# ESP32_2_0_2024-08-18.net
KiCad netlist of a schematic drawn in EasyEDA Pro
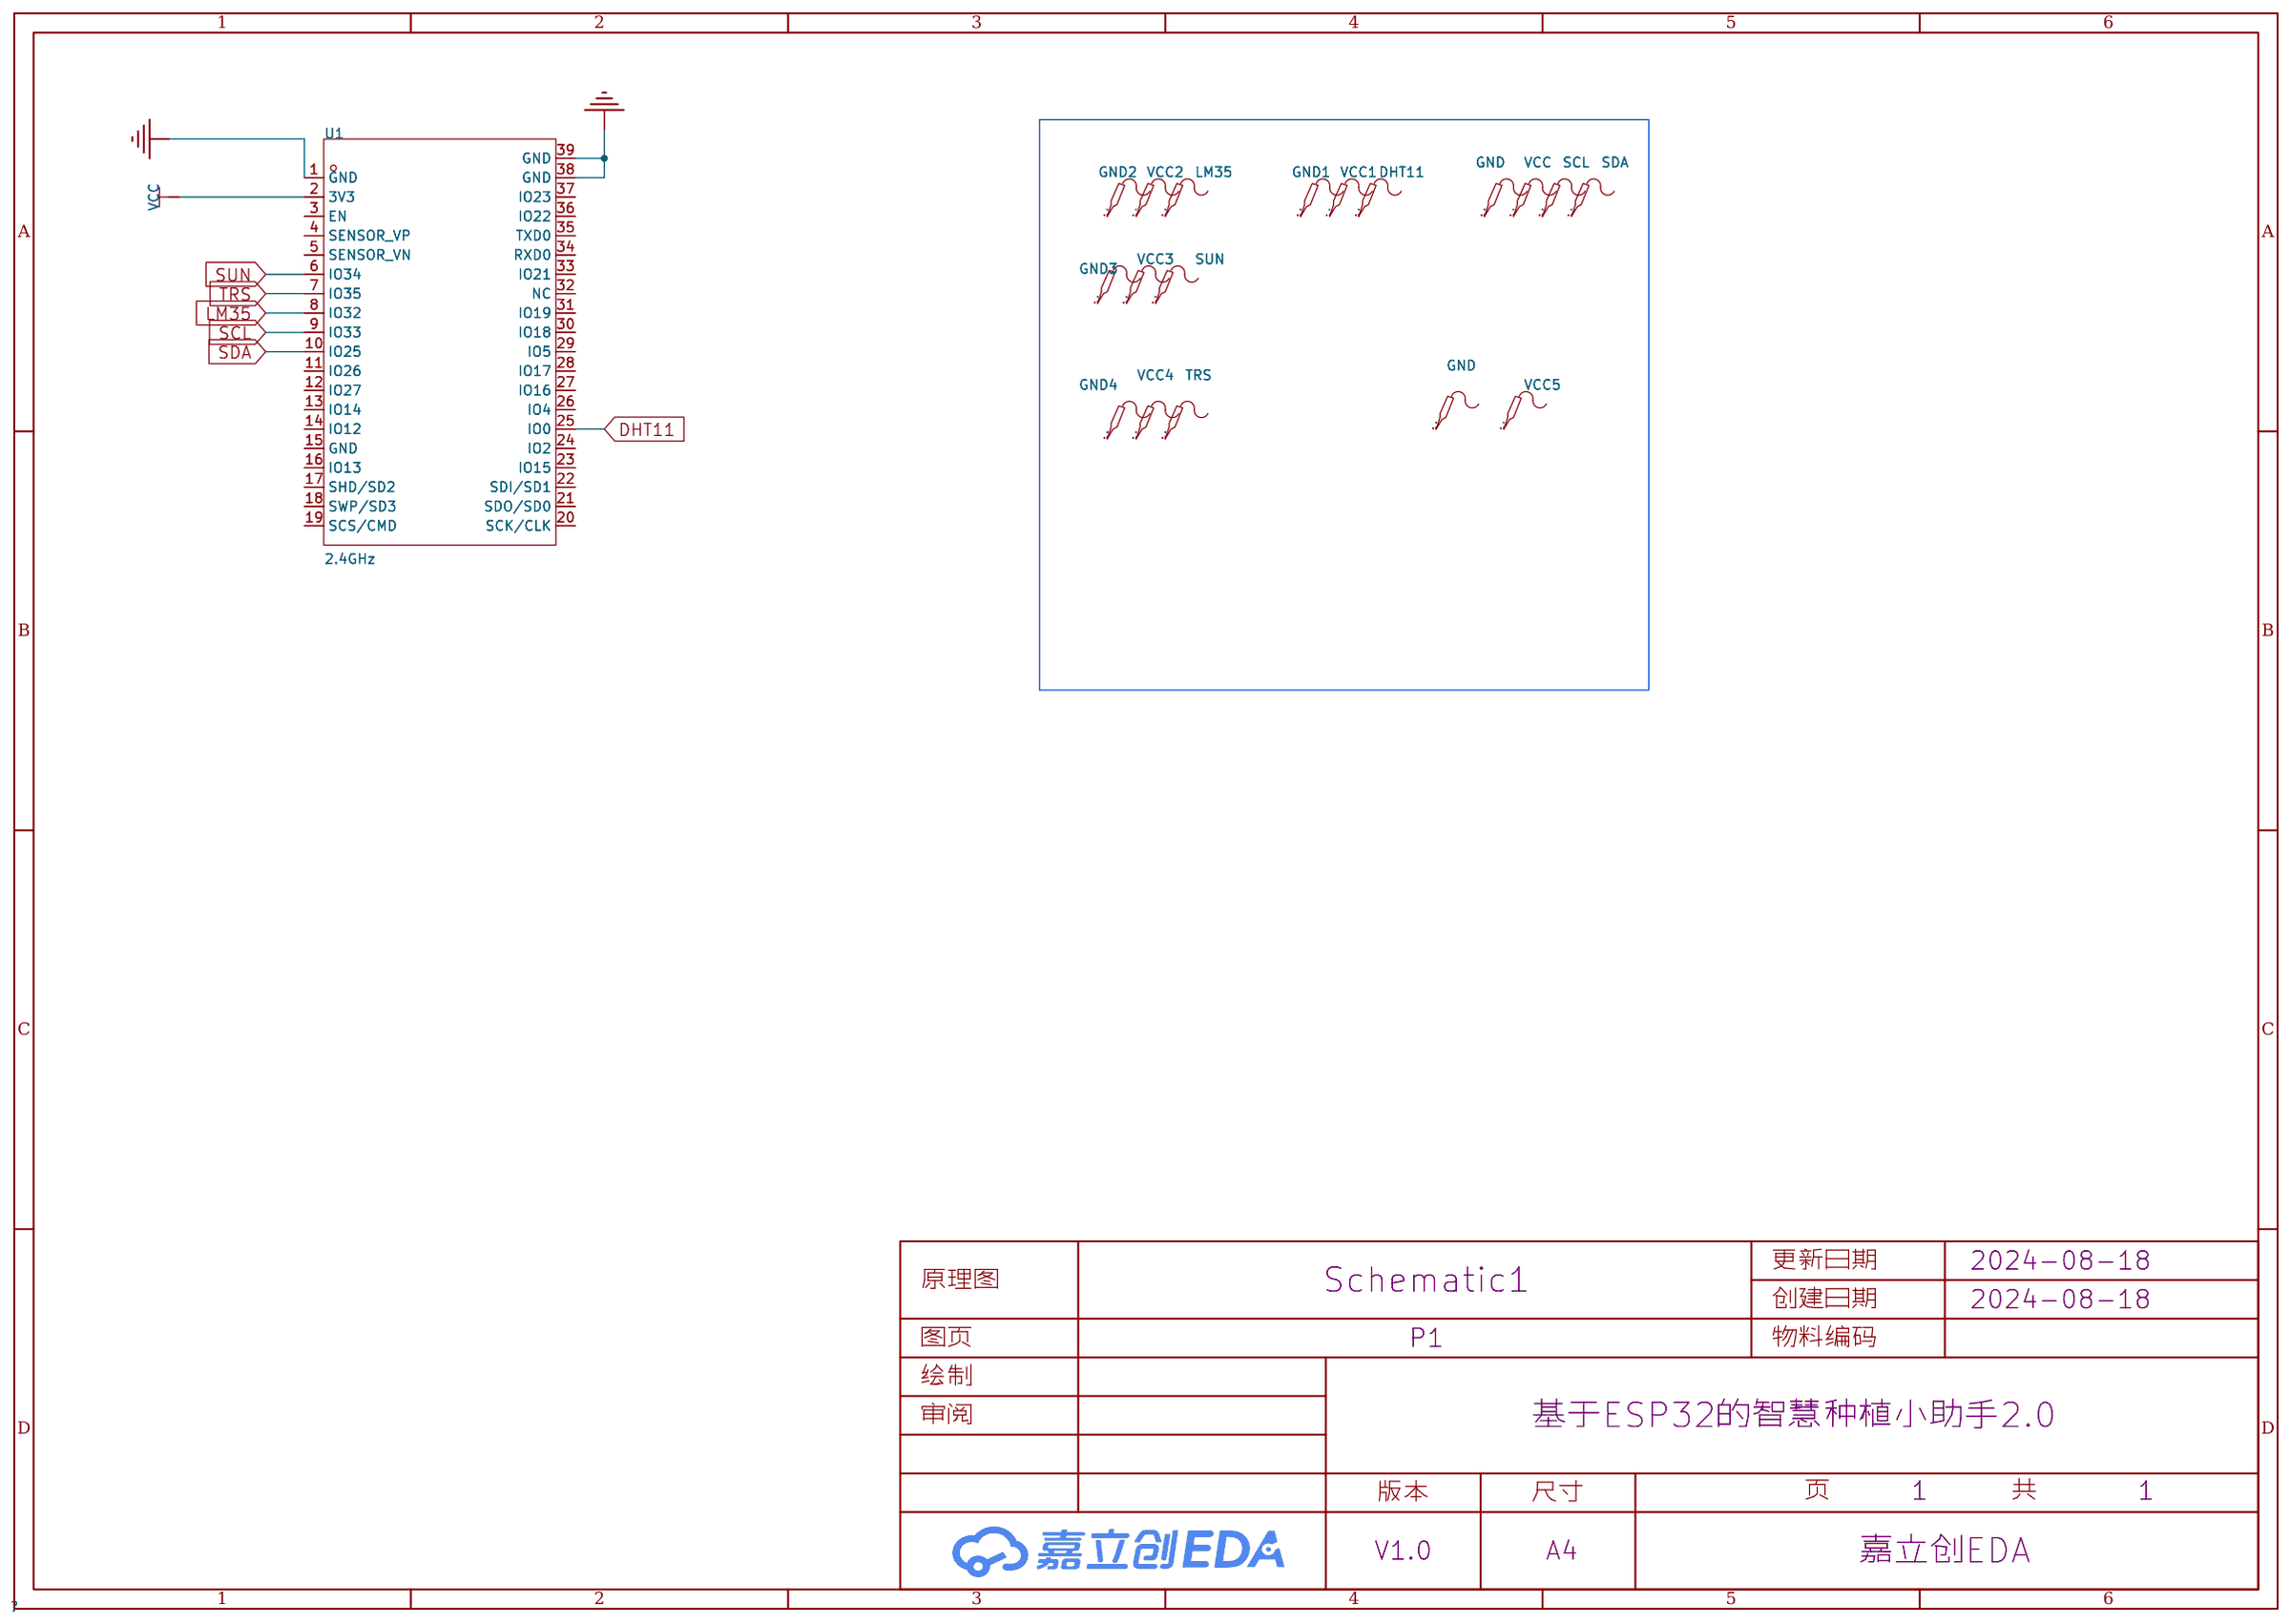
[diagram p0: schematic sheet]

(export (version "E")
  (design (tool "Eeschema 10.0.6"))
  (components
    (comp (ref "DHT11")
      (value "~")
      (footprint "easyedapro:Test-Point-0.5mm")
      (description "Test Point 测试点")
      (libsource (lib "easyedapro") (part "Test-Point"))
    )
    (comp (ref "GND")
      (value "~")
      (footprint "easyedapro:Test-Point-0.5mm")
      (description "Test Point 测试点")
      (libsource (lib "easyedapro") (part "Test-Point"))
    )
    (comp (ref "GND1")
      (value "~")
      (footprint "easyedapro:Test-Point-0.5mm")
      (description "Test Point 测试点")
      (libsource (lib "easyedapro") (part "Test-Point"))
    )
    (comp (ref "GND2")
      (value "~")
      (footprint "easyedapro:Test-Point-0.5mm")
      (description "Test Point 测试点")
      (libsource (lib "easyedapro") (part "Test-Point"))
    )
    (comp (ref "GND3")
      (value "~")
      (footprint "easyedapro:Test-Point-0.5mm")
      (description "Test Point 测试点")
      (libsource (lib "easyedapro") (part "Test-Point"))
    )
    (comp (ref "GND4")
      (value "~")
      (footprint "easyedapro:Test-Point-0.5mm")
      (description "Test Point 测试点")
      (libsource (lib "easyedapro") (part "Test-Point"))
    )
    (comp (ref "LM35")
      (value "~")
      (footprint "easyedapro:Test-Point-0.5mm")
      (description "Test Point 测试点")
      (libsource (lib "easyedapro") (part "Test-Point"))
    )
    (comp (ref "SCL")
      (value "~")
      (footprint "easyedapro:Test-Point-0.5mm")
      (description "Test Point 测试点")
      (libsource (lib "easyedapro") (part "Test-Point"))
    )
    (comp (ref "SDA")
      (value "~")
      (footprint "easyedapro:Test-Point-0.5mm")
      (description "Test Point 测试点")
      (libsource (lib "easyedapro") (part "Test-Point"))
    )
    (comp (ref "SUN")
      (value "~")
      (footprint "easyedapro:Test-Point-0.5mm")
      (description "Test Point 测试点")
      (libsource (lib "easyedapro") (part "Test-Point"))
    )
    (comp (ref "TP1")
      (value "GND")
      (footprint "easyedapro:Test-Point-0.5mm")
      (description "Test Point 测试点")
      (libsource (lib "easyedapro") (part "Test-Point"))
    )
    (comp (ref "TRS")
      (value "~")
      (footprint "easyedapro:Test-Point-0.5mm")
      (description "Test Point 测试点")
      (libsource (lib "easyedapro") (part "Test-Point"))
    )
    (comp (ref "U1")
      (value "2.4GHz")
      (footprint "easyedapro:WIFIM-SMD_39P-L25.5-W18.0-P1.27")
      (description "核心处理器:ESP32-D0WD芯片;频率:2.4GHz;发射功率:18.5dBm;")
      (fields
        (field (name "Manufacturer Part") "ESP32-WROOM-32D(M113DH3200PH3Q0)")
        (field (name "Manufacturer") "ESPRESSIF(乐鑫)")
      )
      (libsource (lib "easyedapro") (part "ESP32-WROOM-32D(M113DH3200PH3Q0)"))
    )
    (comp (ref "VCC")
      (value "~")
      (footprint "easyedapro:Test-Point-0.5mm")
      (description "Test Point 测试点")
      (libsource (lib "easyedapro") (part "Test-Point"))
    )
    (comp (ref "VCC1")
      (value "~")
      (footprint "easyedapro:Test-Point-0.5mm")
      (description "Test Point 测试点")
      (libsource (lib "easyedapro") (part "Test-Point"))
    )
    (comp (ref "VCC2")
      (value "~")
      (footprint "easyedapro:Test-Point-0.5mm")
      (description "Test Point 测试点")
      (libsource (lib "easyedapro") (part "Test-Point"))
    )
    (comp (ref "VCC3")
      (value "~")
      (footprint "easyedapro:Test-Point-0.5mm")
      (description "Test Point 测试点")
      (libsource (lib "easyedapro") (part "Test-Point"))
    )
    (comp (ref "VCC4")
      (value "~")
      (footprint "easyedapro:Test-Point-0.5mm")
      (description "Test Point 测试点")
      (libsource (lib "easyedapro") (part "Test-Point"))
    )
    (comp (ref "VCC5")
      (value "~")
      (footprint "easyedapro:Test-Point-0.5mm")
      (description "Test Point 测试点")
      (libsource (lib "easyedapro") (part "Test-Point"))
    )
  )
  (nets
    (net (code "1") (name "DHT11") (class "Default")
      (node (ref "U1") (pin "25") (pinfunction "IO0_25") (pintype "unspecified"))
    )
    (net (code "2") (name "GND") (class "Default")
      (node (ref "U1") (pin "1") (pinfunction "GND_1") (pintype "unspecified"))
      (node (ref "U1") (pin "38") (pinfunction "GND_38") (pintype "unspecified"))
      (node (ref "U1") (pin "39") (pinfunction "GND_39") (pintype "unspecified"))
    )
    (net (code "3") (name "LM35") (class "Default")
      (node (ref "U1") (pin "8") (pinfunction "IO32_8") (pintype "unspecified"))
    )
    (net (code "4") (name "SCL") (class "Default")
      (node (ref "U1") (pin "9") (pinfunction "IO33_9") (pintype "unspecified"))
    )
    (net (code "5") (name "SDA") (class "Default")
      (node (ref "U1") (pin "10") (pinfunction "IO25_10") (pintype "unspecified"))
    )
    (net (code "6") (name "SUN") (class "Default")
      (node (ref "U1") (pin "6") (pinfunction "IO34_6") (pintype "unspecified"))
    )
    (net (code "7") (name "TRS") (class "Default")
      (node (ref "U1") (pin "7") (pinfunction "IO35_7") (pintype "unspecified"))
    )
    (net (code "8") (name "VCC") (class "Default")
      (node (ref "U1") (pin "2") (pinfunction "3V3_2") (pintype "unspecified"))
    )
    (net (code "9") (name "unconnected-(DHT11-Pad1)") (class "Default")
      (node (ref "DHT11") (pin "1") (pinfunction "1_1") (pintype "input"))
    )
    (net (code "10") (name "unconnected-(GND-Pad1)") (class "Default")
      (node (ref "GND") (pin "1") (pinfunction "1_1") (pintype "input"))
    )
    (net (code "11") (name "unconnected-(GND1-Pad1)") (class "Default")
      (node (ref "GND1") (pin "1") (pinfunction "1_1") (pintype "input"))
    )
    (net (code "12") (name "unconnected-(GND2-Pad1)") (class "Default")
      (node (ref "GND2") (pin "1") (pinfunction "1_1") (pintype "input"))
    )
    (net (code "13") (name "unconnected-(GND3-Pad1)") (class "Default")
      (node (ref "GND3") (pin "1") (pinfunction "1_1") (pintype "input"))
    )
    (net (code "14") (name "unconnected-(GND4-Pad1)") (class "Default")
      (node (ref "GND4") (pin "1") (pinfunction "1_1") (pintype "input"))
    )
    (net (code "15") (name "unconnected-(LM35-Pad1)") (class "Default")
      (node (ref "LM35") (pin "1") (pinfunction "1_1") (pintype "input"))
    )
    (net (code "16") (name "unconnected-(SCL-Pad1)") (class "Default")
      (node (ref "SCL") (pin "1") (pinfunction "1_1") (pintype "input"))
    )
    (net (code "17") (name "unconnected-(SDA-Pad1)") (class "Default")
      (node (ref "SDA") (pin "1") (pinfunction "1_1") (pintype "input"))
    )
    (net (code "18") (name "unconnected-(SUN-Pad1)") (class "Default")
      (node (ref "SUN") (pin "1") (pinfunction "1_1") (pintype "input"))
    )
    (net (code "19") (name "unconnected-(TP1-Pad1)") (class "Default")
      (node (ref "TP1") (pin "1") (pinfunction "1_1") (pintype "input"))
    )
    (net (code "20") (name "unconnected-(TRS-Pad1)") (class "Default")
      (node (ref "TRS") (pin "1") (pinfunction "1_1") (pintype "input"))
    )
    (net (code "21") (name "unconnected-(U1-EN-Pad3)") (class "Default")
      (node (ref "U1") (pin "3") (pinfunction "EN_3") (pintype "unspecified"))
    )
    (net (code "22") (name "unconnected-(U1-GND-Pad15)") (class "Default")
      (node (ref "U1") (pin "15") (pinfunction "GND_15") (pintype "unspecified"))
    )
    (net (code "23") (name "unconnected-(U1-IO2-Pad24)") (class "Default")
      (node (ref "U1") (pin "24") (pinfunction "IO2_24") (pintype "unspecified"))
    )
    (net (code "24") (name "unconnected-(U1-IO4-Pad26)") (class "Default")
      (node (ref "U1") (pin "26") (pinfunction "IO4_26") (pintype "unspecified"))
    )
    (net (code "25") (name "unconnected-(U1-IO5-Pad29)") (class "Default")
      (node (ref "U1") (pin "29") (pinfunction "IO5_29") (pintype "unspecified"))
    )
    (net (code "26") (name "unconnected-(U1-IO12-Pad14)") (class "Default")
      (node (ref "U1") (pin "14") (pinfunction "IO12_14") (pintype "unspecified"))
    )
    (net (code "27") (name "unconnected-(U1-IO13-Pad16)") (class "Default")
      (node (ref "U1") (pin "16") (pinfunction "IO13_16") (pintype "unspecified"))
    )
    (net (code "28") (name "unconnected-(U1-IO14-Pad13)") (class "Default")
      (node (ref "U1") (pin "13") (pinfunction "IO14_13") (pintype "unspecified"))
    )
    (net (code "29") (name "unconnected-(U1-IO15-Pad23)") (class "Default")
      (node (ref "U1") (pin "23") (pinfunction "IO15_23") (pintype "unspecified"))
    )
    (net (code "30") (name "unconnected-(U1-IO16-Pad27)") (class "Default")
      (node (ref "U1") (pin "27") (pinfunction "IO16_27") (pintype "unspecified"))
    )
    (net (code "31") (name "unconnected-(U1-IO17-Pad28)") (class "Default")
      (node (ref "U1") (pin "28") (pinfunction "IO17_28") (pintype "unspecified"))
    )
    (net (code "32") (name "unconnected-(U1-IO18-Pad30)") (class "Default")
      (node (ref "U1") (pin "30") (pinfunction "IO18_30") (pintype "unspecified"))
    )
    (net (code "33") (name "unconnected-(U1-IO19-Pad31)") (class "Default")
      (node (ref "U1") (pin "31") (pinfunction "IO19_31") (pintype "unspecified"))
    )
    (net (code "34") (name "unconnected-(U1-IO21-Pad33)") (class "Default")
      (node (ref "U1") (pin "33") (pinfunction "IO21_33") (pintype "unspecified"))
    )
    (net (code "35") (name "unconnected-(U1-IO22-Pad36)") (class "Default")
      (node (ref "U1") (pin "36") (pinfunction "IO22_36") (pintype "unspecified"))
    )
    (net (code "36") (name "unconnected-(U1-IO23-Pad37)") (class "Default")
      (node (ref "U1") (pin "37") (pinfunction "IO23_37") (pintype "unspecified"))
    )
    (net (code "37") (name "unconnected-(U1-IO26-Pad11)") (class "Default")
      (node (ref "U1") (pin "11") (pinfunction "IO26_11") (pintype "unspecified"))
    )
    (net (code "38") (name "unconnected-(U1-IO27-Pad12)") (class "Default")
      (node (ref "U1") (pin "12") (pinfunction "IO27_12") (pintype "unspecified"))
    )
    (net (code "39") (name "unconnected-(U1-NC-Pad32)") (class "Default")
      (node (ref "U1") (pin "32") (pinfunction "NC_32") (pintype "unspecified"))
    )
    (net (code "40") (name "unconnected-(U1-RXD0-Pad34)") (class "Default")
      (node (ref "U1") (pin "34") (pinfunction "RXD0_34") (pintype "unspecified"))
    )
    (net (code "41") (name "unconnected-(U1-SCK{slash}CLK-Pad20)") (class "Default")
      (node (ref "U1") (pin "20") (pinfunction "SCK/CLK_20") (pintype "unspecified"))
    )
    (net (code "42") (name "unconnected-(U1-SCS{slash}CMD-Pad19)") (class "Default")
      (node (ref "U1") (pin "19") (pinfunction "SCS/CMD_19") (pintype "unspecified"))
    )
    (net (code "43") (name "unconnected-(U1-SDI{slash}SD1-Pad22)") (class "Default")
      (node (ref "U1") (pin "22") (pinfunction "SDI/SD1_22") (pintype "unspecified"))
    )
    (net (code "44") (name "unconnected-(U1-SDO{slash}SD0-Pad21)") (class "Default")
      (node (ref "U1") (pin "21") (pinfunction "SDO/SD0_21") (pintype "unspecified"))
    )
    (net (code "45") (name "unconnected-(U1-SENSOR_VN-Pad5)") (class "Default")
      (node (ref "U1") (pin "5") (pinfunction "SENSOR_VN_5") (pintype "unspecified"))
    )
    (net (code "46") (name "unconnected-(U1-SENSOR_VP-Pad4)") (class "Default")
      (node (ref "U1") (pin "4") (pinfunction "SENSOR_VP_4") (pintype "unspecified"))
    )
    (net (code "47") (name "unconnected-(U1-SHD{slash}SD2-Pad17)") (class "Default")
      (node (ref "U1") (pin "17") (pinfunction "SHD/SD2_17") (pintype "unspecified"))
    )
    (net (code "48") (name "unconnected-(U1-SWP{slash}SD3-Pad18)") (class "Default")
      (node (ref "U1") (pin "18") (pinfunction "SWP/SD3_18") (pintype "unspecified"))
    )
    (net (code "49") (name "unconnected-(U1-TXD0-Pad35)") (class "Default")
      (node (ref "U1") (pin "35") (pinfunction "TXD0_35") (pintype "unspecified"))
    )
    (net (code "50") (name "unconnected-(VCC-Pad1)") (class "Default")
      (node (ref "VCC") (pin "1") (pinfunction "1_1") (pintype "input"))
    )
    (net (code "51") (name "unconnected-(VCC1-Pad1)") (class "Default")
      (node (ref "VCC1") (pin "1") (pinfunction "1_1") (pintype "input"))
    )
    (net (code "52") (name "unconnected-(VCC2-Pad1)") (class "Default")
      (node (ref "VCC2") (pin "1") (pinfunction "1_1") (pintype "input"))
    )
    (net (code "53") (name "unconnected-(VCC3-Pad1)") (class "Default")
      (node (ref "VCC3") (pin "1") (pinfunction "1_1") (pintype "input"))
    )
    (net (code "54") (name "unconnected-(VCC4-Pad1)") (class "Default")
      (node (ref "VCC4") (pin "1") (pinfunction "1_1") (pintype "input"))
    )
    (net (code "55") (name "unconnected-(VCC5-Pad1)") (class "Default")
      (node (ref "VCC5") (pin "1") (pinfunction "1_1") (pintype "input"))
    )
  )
)
